# led_brick_smd.net
KiCad netlist of a schematic drawn in EAGLE
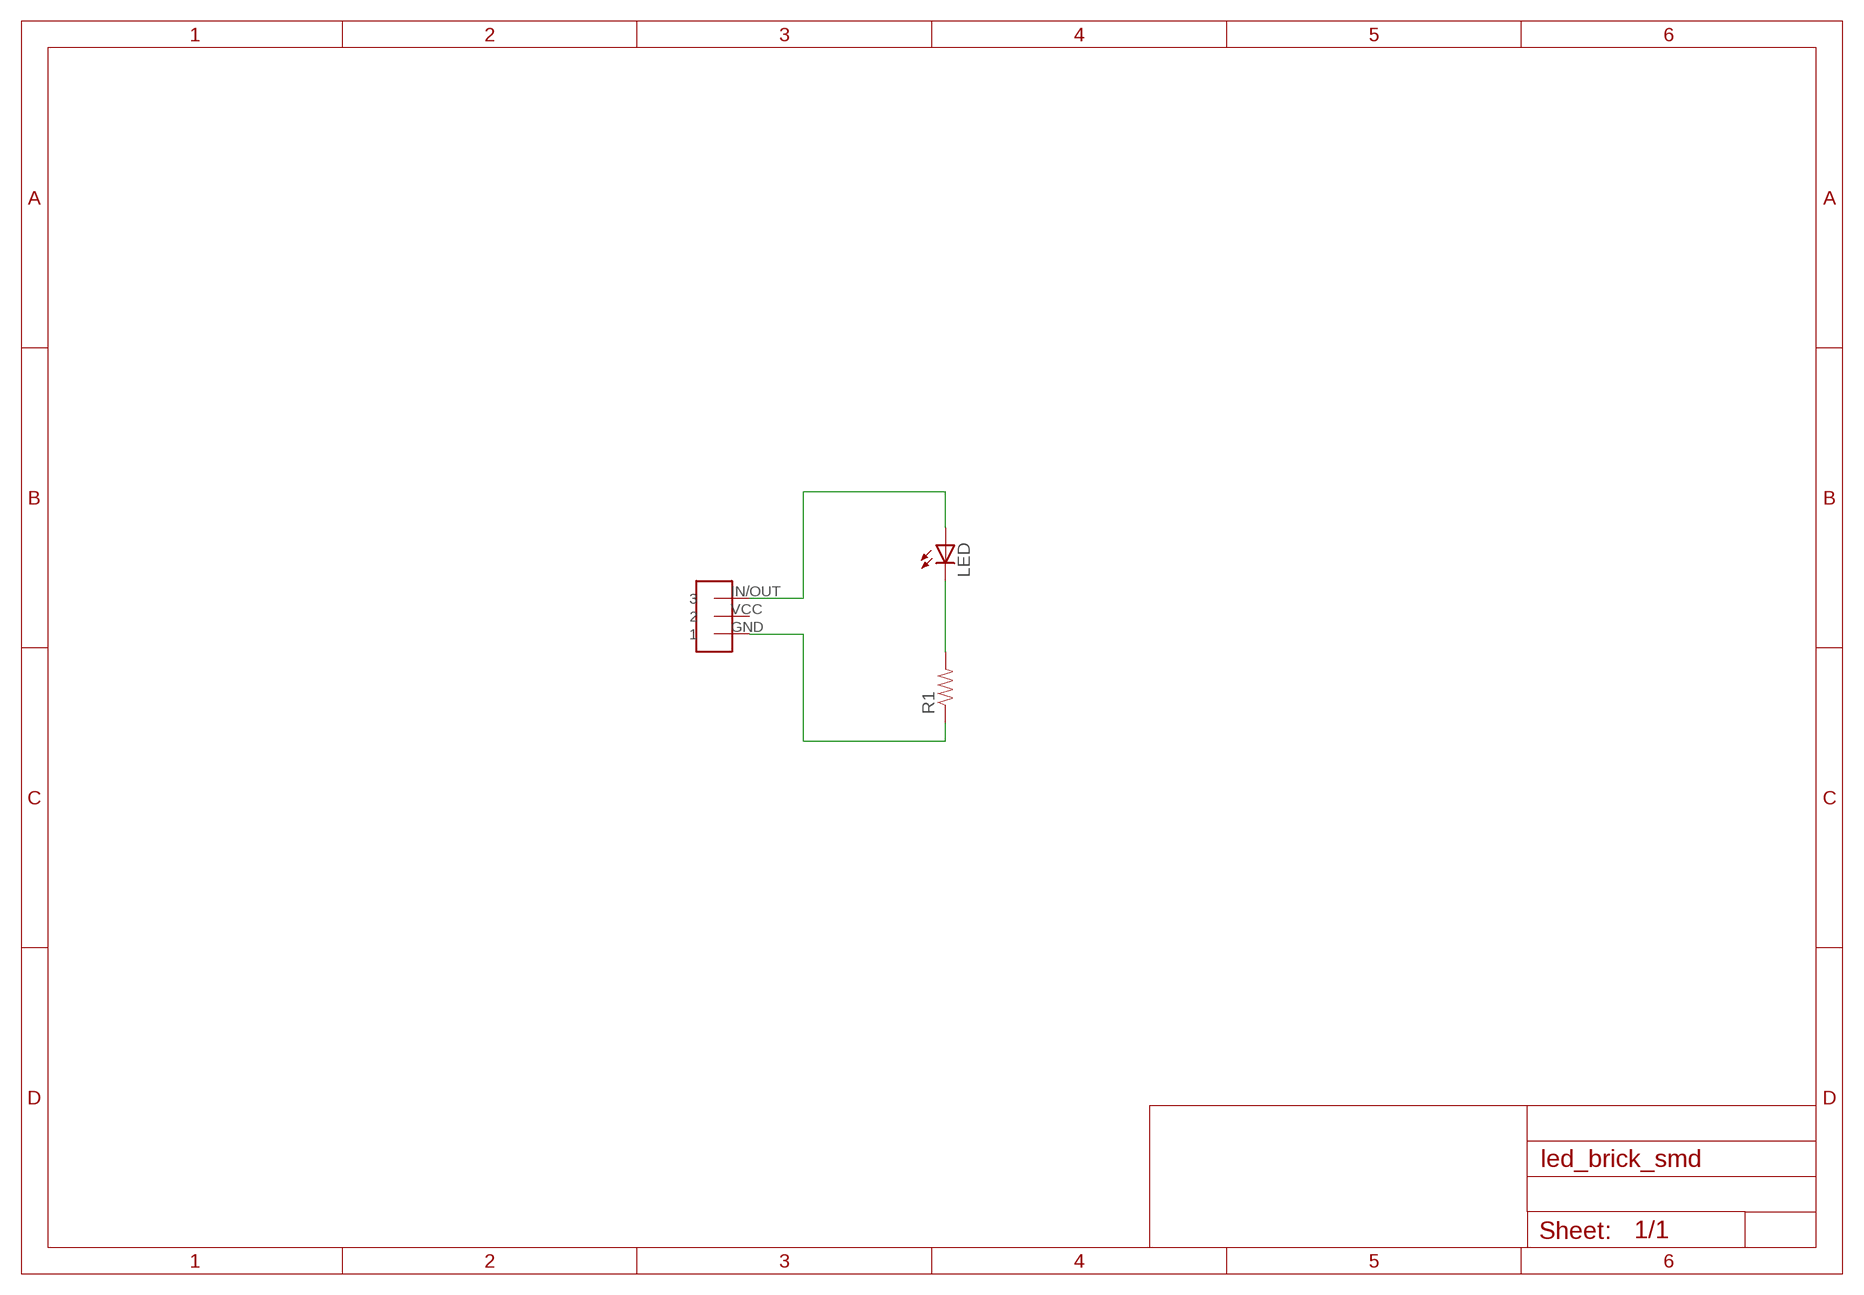
[diagram p0: schematic, sheet 1]

(export (version "E")
  (design (tool "Eeschema 10.0.6"))
  (components
    (comp (ref "LED")
      (value "LEDCHIP-LED0603")
      (footprint "eagle-import:CHIP-LED0603")
      (libsource (lib "eagle-import") (part "LEDCHIP-LED0603"))
    )
    (comp (ref "R1")
      (value "RESISTOR0603-RES")
      (footprint "eagle-import:0603-RES")
      (libsource (lib "eagle-import") (part "RESISTOR0603-RES"))
    )
    (comp (ref "U$1")
      (value "BRICK-3PIN")
      (footprint "eagle-import:BRICK_3PIN")
      (libsource (lib "eagle-import") (part "BRICK-3PIN"))
    )
  )
  (nets
    (net (code "1") (name "Net-(LED-PadC)") (class "Default")
      (node (ref "LED") (pin "C") (pinfunction "C_C") (pintype "passive"))
      (node (ref "R1") (pin "2") (pinfunction "2_2") (pintype "passive"))
    )
    (net (code "2") (name "Net-(U$1-1)") (class "Default")
      (node (ref "R1") (pin "1") (pinfunction "1_1") (pintype "passive"))
      (node (ref "U$1") (pin "GND") (pinfunction "1_GND") (pintype "bidirectional"))
    )
    (net (code "3") (name "Net-(U$1-3)") (class "Default")
      (node (ref "LED") (pin "A") (pinfunction "A_A") (pintype "passive"))
      (node (ref "U$1") (pin "IN/OUT") (pinfunction "3_IN/OUT") (pintype "bidirectional"))
    )
    (net (code "4") (name "unconnected-(U$1-2-PadVCC)") (class "Default")
      (node (ref "U$1") (pin "VCC") (pinfunction "2_VCC") (pintype "bidirectional"))
    )
  )
)
